# Sheet1.net
KiCad netlist of a schematic drawn in Altium Designer
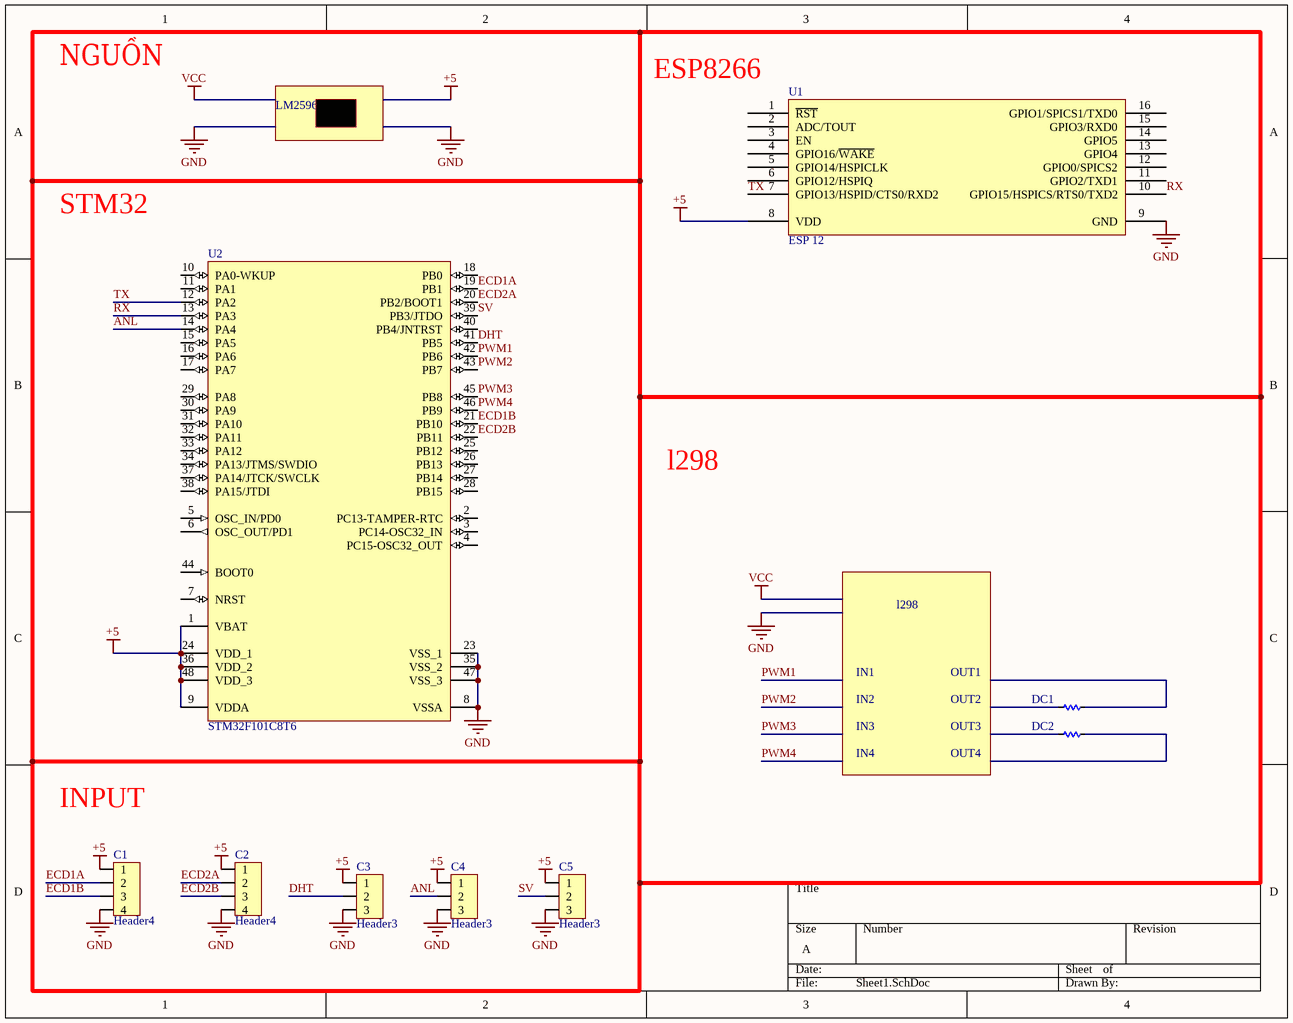
[diagram p0: Sheet1.SchDoc]

(export (version "E")
  (design (tool "Eeschema 10.0.6"))
  (components
    (comp (ref "C1")
      (value "Header4")
      (footprint "HDR4")
      (description "Header IDC, 4 x 1 Pin Vertical 2.54mm Pitch (Non-Boxed, Male)")
      (fields
        (field (name "MANUFACTURER") "Würth Elektronik eiSos GmbH")
        (field (name "PARTNO") "613002143121")
        (field (name "CREATED BY") "Karrer Zheng")
      )
      (libsource (lib "LIBRARY1") (part "Header4"))
    )
    (comp (ref "C2")
      (value "Header4")
      (footprint "HDR4")
      (description "Header IDC, 4 x 1 Pin Vertical 2.54mm Pitch (Non-Boxed, Male)")
      (fields
        (field (name "MANUFACTURER") "Würth Elektronik eiSos GmbH")
        (field (name "PARTNO") "613002143121")
        (field (name "CREATED BY") "Karrer Zheng")
      )
      (libsource (lib "LIBRARY1") (part "Header4"))
    )
    (comp (ref "C3")
      (value "Header3")
      (footprint "HDR3")
      (description "Header IDC, 3 x 1 Pin Vertical 2.54mm Pitch (Non-Boxed, Male)")
      (fields
        (field (name "MANUFACTURER") "Würth Elektronik eiSos GmbH")
        (field (name "PARTNO") "613002143121")
        (field (name "CREATED BY") "Karrer Zheng")
      )
      (libsource (lib "LIBRARY1") (part "Header3"))
    )
    (comp (ref "C4")
      (value "Header3")
      (footprint "HDR3")
      (description "Header IDC, 3 x 1 Pin Vertical 2.54mm Pitch (Non-Boxed, Male)")
      (fields
        (field (name "MANUFACTURER") "Würth Elektronik eiSos GmbH")
        (field (name "PARTNO") "613002143121")
        (field (name "CREATED BY") "Karrer Zheng")
      )
      (libsource (lib "LIBRARY1") (part "Header3"))
    )
    (comp (ref "C5")
      (value "Header3")
      (footprint "HDR3")
      (description "Header IDC, 3 x 1 Pin Vertical 2.54mm Pitch (Non-Boxed, Male)")
      (fields
        (field (name "MANUFACTURER") "Würth Elektronik eiSos GmbH")
        (field (name "PARTNO") "613002143121")
        (field (name "CREATED BY") "Karrer Zheng")
      )
      (libsource (lib "LIBRARY1") (part "Header3"))
    )
    (comp (ref "DC1")
      (value "Res")
      (footprint "RES-1/2W")
      (fields
        (field (name "MANUFACTURER") "Generic Components")
        (field (name "PUBLISHER") "Altium Hobart Technology Centre")
      )
      (libsource (lib "Library") (part "Res"))
    )
    (comp (ref "DC2")
      (value "Res")
      (footprint "RES-1/2W")
      (fields
        (field (name "MANUFACTURER") "Generic Components")
        (field (name "PUBLISHER") "Altium Hobart Technology Centre")
      )
      (libsource (lib "Library") (part "Res"))
    )
    (comp (ref "U1")
      (value "ESP 12")
      (footprint "ESP12")
      (description "ESP-12 Wi-Fi Module by AI-Thinker")
      (libsource (lib "Library") (part "ESP_12"))
    )
    (comp (ref "U2")
      (value "STM32F101C8T6")
      (footprint "TQFP48")
      (description "STM32 ARM-based 32-bit MCU with 32 Kbytes Flash, 48-pin LQFP, Industrial Temperature")
      (fields (field (name "PUBLISHER") "Altium Limited"))
      (libsource (lib "LIBRARY1") (part "STM32F101C6T6"))
    )
  )
  (nets
    (net (code "1") (name "+5") (class "Default")
      (node (ref "C1") (pin "1") (pinfunction "1_1") (pintype "passive"))
      (node (ref "C2") (pin "1") (pinfunction "1_1") (pintype "passive"))
      (node (ref "C3") (pin "1") (pinfunction "1_1") (pintype "passive"))
      (node (ref "C4") (pin "1") (pinfunction "1_1") (pintype "passive"))
      (node (ref "C5") (pin "1") (pinfunction "1_1") (pintype "passive"))
      (node (ref "U1") (pin "8") (pinfunction "VDD_8") (pintype "passive"))
      (node (ref "U2") (pin "1") (pinfunction "VBAT_1") (pintype "power_in"))
      (node (ref "U2") (pin "24") (pinfunction "VDD_1_24") (pintype "power_in"))
      (node (ref "U2") (pin "36") (pinfunction "VDD_2_36") (pintype "power_in"))
      (node (ref "U2") (pin "48") (pinfunction "VDD_3_48") (pintype "power_in"))
      (node (ref "U2") (pin "9") (pinfunction "VDDA_9") (pintype "power_in"))
    )
    (net (code "2") (name "/ANL") (class "Default")
      (node (ref "C4") (pin "2") (pinfunction "2_2") (pintype "passive"))
      (node (ref "U2") (pin "14") (pinfunction "PA4_14") (pintype "bidirectional"))
    )
    (net (code "3") (name "/DHT") (class "Default")
      (node (ref "C3") (pin "2") (pinfunction "2_2") (pintype "passive"))
      (node (ref "U2") (pin "41") (pinfunction "PB5_41") (pintype "bidirectional"))
    )
    (net (code "4") (name "/ECD1A") (class "Default")
      (node (ref "C1") (pin "2") (pinfunction "2_2") (pintype "passive"))
      (node (ref "U2") (pin "19") (pinfunction "PB1_19") (pintype "bidirectional"))
    )
    (net (code "5") (name "/ECD1B") (class "Default")
      (node (ref "C1") (pin "3") (pinfunction "3_3") (pintype "passive"))
      (node (ref "U2") (pin "21") (pinfunction "PB10_21") (pintype "bidirectional"))
    )
    (net (code "6") (name "/ECD2A") (class "Default")
      (node (ref "C2") (pin "2") (pinfunction "2_2") (pintype "passive"))
      (node (ref "U2") (pin "20") (pinfunction "PB2/BOOT1_20") (pintype "bidirectional"))
    )
    (net (code "7") (name "/ECD2B") (class "Default")
      (node (ref "C2") (pin "3") (pinfunction "3_3") (pintype "passive"))
      (node (ref "U2") (pin "22") (pinfunction "PB11_22") (pintype "bidirectional"))
    )
    (net (code "8") (name "/PWM1") (class "Default")
      (node (ref "U2") (pin "42") (pinfunction "PB6_42") (pintype "bidirectional"))
    )
    (net (code "9") (name "/PWM2") (class "Default")
      (node (ref "U2") (pin "43") (pinfunction "PB7_43") (pintype "bidirectional"))
    )
    (net (code "10") (name "/PWM3") (class "Default")
      (node (ref "U2") (pin "45") (pinfunction "PB8_45") (pintype "bidirectional"))
    )
    (net (code "11") (name "/PWM4") (class "Default")
      (node (ref "U2") (pin "46") (pinfunction "PB9_46") (pintype "bidirectional"))
    )
    (net (code "12") (name "/RX") (class "Default")
      (node (ref "U1") (pin "10") (pinfunction "GPIO15/HSPICS/RTS0/TXD2_10") (pintype "passive"))
      (node (ref "U2") (pin "13") (pinfunction "PA3_13") (pintype "bidirectional"))
    )
    (net (code "13") (name "/SV") (class "Default")
      (node (ref "C5") (pin "2") (pinfunction "2_2") (pintype "passive"))
      (node (ref "U2") (pin "39") (pinfunction "PB3/JTDO_39") (pintype "bidirectional"))
    )
    (net (code "14") (name "/TX") (class "Default")
      (node (ref "U1") (pin "7") (pinfunction "GPIO13/HSPID/CTS0/RXD2_7") (pintype "passive"))
      (node (ref "U2") (pin "12") (pinfunction "PA2_12") (pintype "bidirectional"))
    )
    (net (code "15") (name "GND") (class "Default")
      (node (ref "C1") (pin "4") (pinfunction "4_4") (pintype "passive"))
      (node (ref "C2") (pin "4") (pinfunction "4_4") (pintype "passive"))
      (node (ref "C3") (pin "3") (pinfunction "3_3") (pintype "passive"))
      (node (ref "C4") (pin "3") (pinfunction "3_3") (pintype "passive"))
      (node (ref "C5") (pin "3") (pinfunction "3_3") (pintype "passive"))
      (node (ref "U1") (pin "9") (pinfunction "GND_9") (pintype "passive"))
      (node (ref "U2") (pin "23") (pinfunction "VSS_1_23") (pintype "power_in"))
      (node (ref "U2") (pin "35") (pinfunction "VSS_2_35") (pintype "power_in"))
      (node (ref "U2") (pin "47") (pinfunction "VSS_3_47") (pintype "power_in"))
      (node (ref "U2") (pin "8") (pinfunction "VSSA_8") (pintype "power_in"))
    )
    (net (code "17") (name "unconnected-(DC1-Pad1)") (class "Default")
      (node (ref "DC1") (pin "1") (pinfunction "1_1") (pintype "passive"))
    )
    (net (code "18") (name "unconnected-(DC1-Pad2)") (class "Default")
      (node (ref "DC1") (pin "2") (pinfunction "2_2") (pintype "passive"))
    )
    (net (code "19") (name "unconnected-(DC2-Pad1)") (class "Default")
      (node (ref "DC2") (pin "1") (pinfunction "1_1") (pintype "passive"))
    )
    (net (code "20") (name "unconnected-(DC2-Pad2)") (class "Default")
      (node (ref "DC2") (pin "2") (pinfunction "2_2") (pintype "passive"))
    )
    (net (code "21") (name "unconnected-(U1-ADC{slash}TOUT-Pad2)") (class "Default")
      (node (ref "U1") (pin "2") (pinfunction "ADC/TOUT_2") (pintype "passive"))
    )
    (net (code "22") (name "unconnected-(U1-EN-Pad3)") (class "Default")
      (node (ref "U1") (pin "3") (pinfunction "EN_3") (pintype "passive"))
    )
    (net (code "23") (name "unconnected-(U1-GPIO0{slash}SPICS2-Pad12)") (class "Default")
      (node (ref "U1") (pin "12") (pinfunction "GPIO0/SPICS2_12") (pintype "passive"))
    )
    (net (code "24") (name "unconnected-(U1-GPIO1{slash}SPICS1{slash}TXD0-Pad16)") (class "Default")
      (node (ref "U1") (pin "16") (pinfunction "GPIO1/SPICS1/TXD0_16") (pintype "passive"))
    )
    (net (code "25") (name "unconnected-(U1-GPIO2{slash}TXD1-Pad11)") (class "Default")
      (node (ref "U1") (pin "11") (pinfunction "GPIO2/TXD1_11") (pintype "passive"))
    )
    (net (code "26") (name "unconnected-(U1-GPIO3{slash}RXD0-Pad15)") (class "Default")
      (node (ref "U1") (pin "15") (pinfunction "GPIO3/RXD0_15") (pintype "passive"))
    )
    (net (code "27") (name "unconnected-(U1-GPIO4-Pad13)") (class "Default")
      (node (ref "U1") (pin "13") (pinfunction "GPIO4_13") (pintype "passive"))
    )
    (net (code "28") (name "unconnected-(U1-GPIO5-Pad14)") (class "Default")
      (node (ref "U1") (pin "14") (pinfunction "GPIO5_14") (pintype "passive"))
    )
    (net (code "29") (name "unconnected-(U1-GPIO12{slash}HSPIQ-Pad6)") (class "Default")
      (node (ref "U1") (pin "6") (pinfunction "GPIO12/HSPIQ_6") (pintype "passive"))
    )
    (net (code "30") (name "unconnected-(U1-GPIO14{slash}HSPICLK-Pad5)") (class "Default")
      (node (ref "U1") (pin "5") (pinfunction "GPIO14/HSPICLK_5") (pintype "passive"))
    )
    (net (code "31") (name "unconnected-(U1-GPIO16{slash}~{WAKE}-Pad4)") (class "Default")
      (node (ref "U1") (pin "4") (pinfunction "GPIO16/~{WAKE}_4") (pintype "passive"))
    )
    (net (code "32") (name "unconnected-(U1-~{RST}-Pad1)") (class "Default")
      (node (ref "U1") (pin "1") (pinfunction "~{RST}_1") (pintype "passive"))
    )
    (net (code "33") (name "unconnected-(U2-BOOT0-Pad44)") (class "Default")
      (node (ref "U2") (pin "44") (pinfunction "BOOT0_44") (pintype "input"))
    )
    (net (code "34") (name "unconnected-(U2-NRST-Pad7)") (class "Default")
      (node (ref "U2") (pin "7") (pinfunction "NRST_7") (pintype "bidirectional"))
    )
    (net (code "35") (name "unconnected-(U2-OSC_IN{slash}PD0-Pad5)") (class "Default")
      (node (ref "U2") (pin "5") (pinfunction "OSC_IN/PD0_5") (pintype "input"))
    )
    (net (code "36") (name "unconnected-(U2-OSC_OUT{slash}PD1-Pad6)") (class "Default")
      (node (ref "U2") (pin "6") (pinfunction "OSC_OUT/PD1_6") (pintype "output"))
    )
    (net (code "37") (name "unconnected-(U2-PA0-WKUP-Pad10)") (class "Default")
      (node (ref "U2") (pin "10") (pinfunction "PA0-WKUP_10") (pintype "bidirectional"))
    )
    (net (code "38") (name "unconnected-(U2-PA1-Pad11)") (class "Default")
      (node (ref "U2") (pin "11") (pinfunction "PA1_11") (pintype "bidirectional"))
    )
    (net (code "39") (name "unconnected-(U2-PA5-Pad15)") (class "Default")
      (node (ref "U2") (pin "15") (pinfunction "PA5_15") (pintype "bidirectional"))
    )
    (net (code "40") (name "unconnected-(U2-PA6-Pad16)") (class "Default")
      (node (ref "U2") (pin "16") (pinfunction "PA6_16") (pintype "bidirectional"))
    )
    (net (code "41") (name "unconnected-(U2-PA7-Pad17)") (class "Default")
      (node (ref "U2") (pin "17") (pinfunction "PA7_17") (pintype "bidirectional"))
    )
    (net (code "42") (name "unconnected-(U2-PA8-Pad29)") (class "Default")
      (node (ref "U2") (pin "29") (pinfunction "PA8_29") (pintype "bidirectional"))
    )
    (net (code "43") (name "unconnected-(U2-PA9-Pad30)") (class "Default")
      (node (ref "U2") (pin "30") (pinfunction "PA9_30") (pintype "bidirectional"))
    )
    (net (code "44") (name "unconnected-(U2-PA10-Pad31)") (class "Default")
      (node (ref "U2") (pin "31") (pinfunction "PA10_31") (pintype "bidirectional"))
    )
    (net (code "45") (name "unconnected-(U2-PA11-Pad32)") (class "Default")
      (node (ref "U2") (pin "32") (pinfunction "PA11_32") (pintype "bidirectional"))
    )
    (net (code "46") (name "unconnected-(U2-PA12-Pad33)") (class "Default")
      (node (ref "U2") (pin "33") (pinfunction "PA12_33") (pintype "bidirectional"))
    )
    (net (code "47") (name "unconnected-(U2-PA13{slash}JTMS{slash}SWDIO-Pad34)") (class "Default")
      (node (ref "U2") (pin "34") (pinfunction "PA13/JTMS/SWDIO_34") (pintype "bidirectional"))
    )
    (net (code "48") (name "unconnected-(U2-PA14{slash}JTCK{slash}SWCLK-Pad37)") (class "Default")
      (node (ref "U2") (pin "37") (pinfunction "PA14/JTCK/SWCLK_37") (pintype "bidirectional"))
    )
    (net (code "49") (name "unconnected-(U2-PA15{slash}JTDI-Pad38)") (class "Default")
      (node (ref "U2") (pin "38") (pinfunction "PA15/JTDI_38") (pintype "bidirectional"))
    )
    (net (code "50") (name "unconnected-(U2-PB0-Pad18)") (class "Default")
      (node (ref "U2") (pin "18") (pinfunction "PB0_18") (pintype "bidirectional"))
    )
    (net (code "51") (name "unconnected-(U2-PB4{slash}JNTRST-Pad40)") (class "Default")
      (node (ref "U2") (pin "40") (pinfunction "PB4/JNTRST_40") (pintype "bidirectional"))
    )
    (net (code "52") (name "unconnected-(U2-PB12-Pad25)") (class "Default")
      (node (ref "U2") (pin "25") (pinfunction "PB12_25") (pintype "bidirectional"))
    )
    (net (code "53") (name "unconnected-(U2-PB13-Pad26)") (class "Default")
      (node (ref "U2") (pin "26") (pinfunction "PB13_26") (pintype "bidirectional"))
    )
    (net (code "54") (name "unconnected-(U2-PB14-Pad27)") (class "Default")
      (node (ref "U2") (pin "27") (pinfunction "PB14_27") (pintype "bidirectional"))
    )
    (net (code "55") (name "unconnected-(U2-PB15-Pad28)") (class "Default")
      (node (ref "U2") (pin "28") (pinfunction "PB15_28") (pintype "bidirectional"))
    )
    (net (code "56") (name "unconnected-(U2-PC13-TAMPER-RTC-Pad2)") (class "Default")
      (node (ref "U2") (pin "2") (pinfunction "PC13-TAMPER-RTC_2") (pintype "bidirectional"))
    )
    (net (code "57") (name "unconnected-(U2-PC14-OSC32_IN-Pad3)") (class "Default")
      (node (ref "U2") (pin "3") (pinfunction "PC14-OSC32_IN_3") (pintype "bidirectional"))
    )
    (net (code "58") (name "unconnected-(U2-PC15-OSC32_OUT-Pad4)") (class "Default")
      (node (ref "U2") (pin "4") (pinfunction "PC15-OSC32_OUT_4") (pintype "bidirectional"))
    )
  )
)
